# Sheet1.net
KiCad netlist of a schematic drawn in Altium Designer
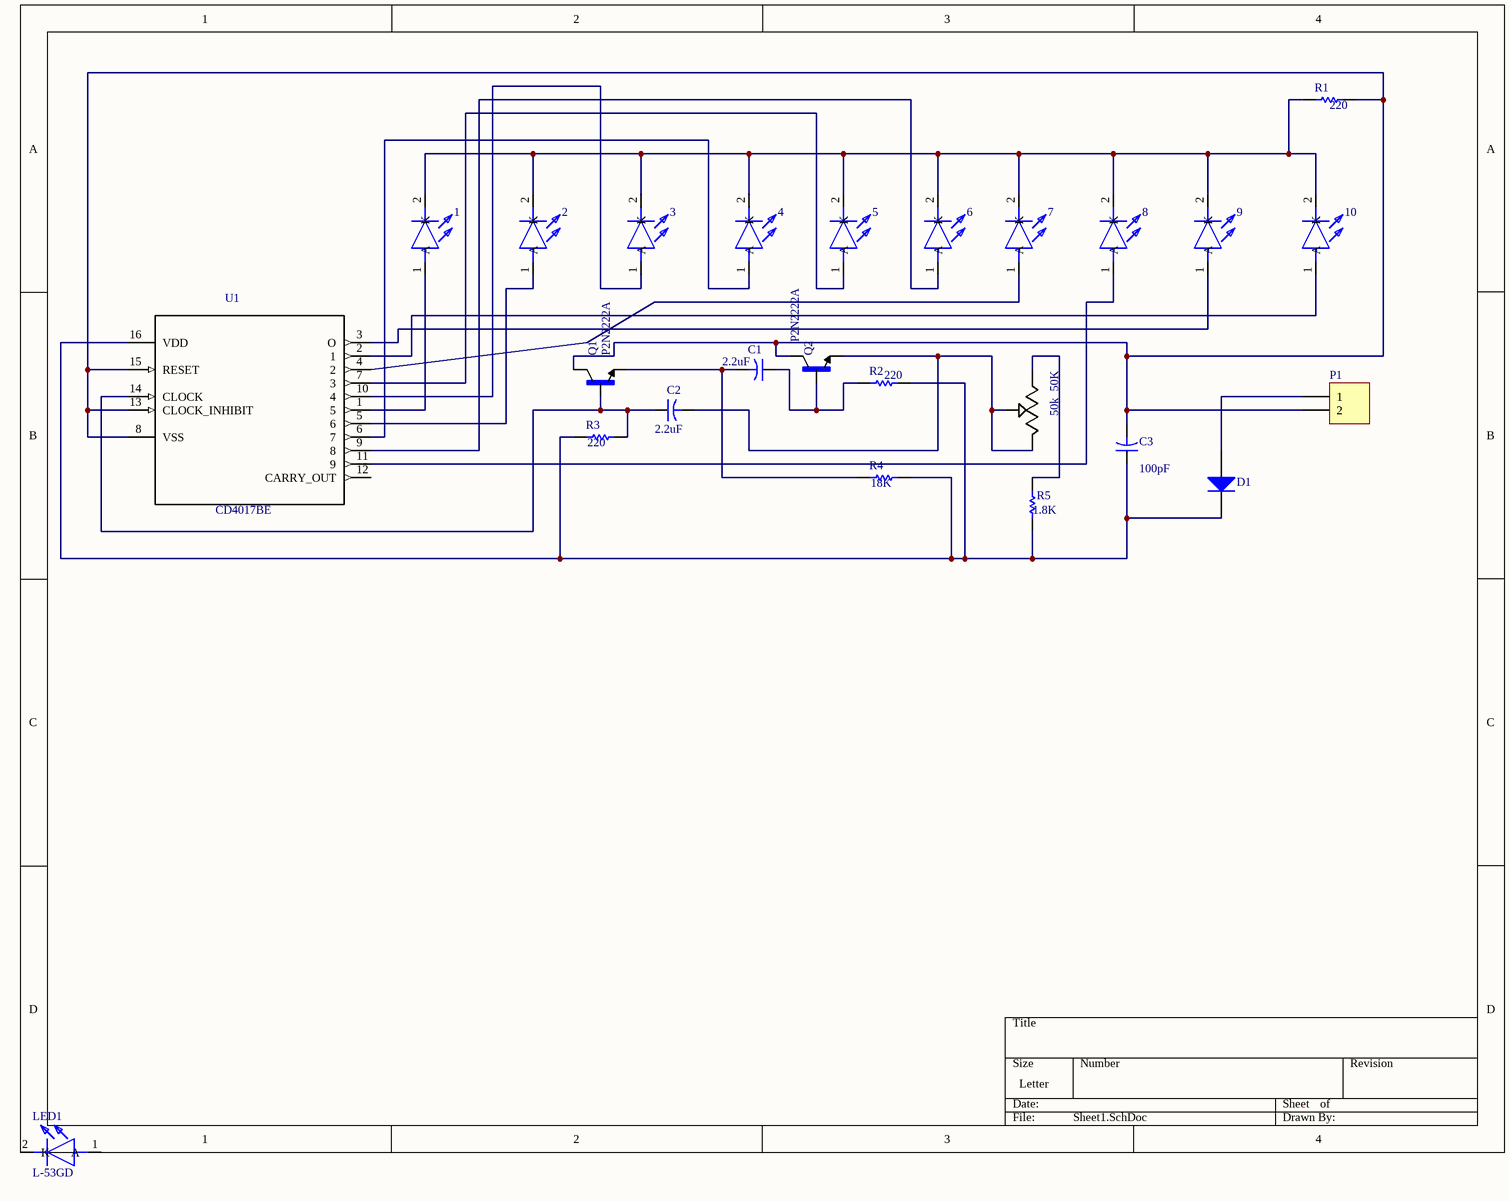
[diagram p0: Sheet1.SchDoc]

(export (version "E")
  (design (tool "Eeschema 10.0.6"))
  (components
    (comp (ref "1")
      (value "L-53GD")
      (footprint "SamacSys:L-53GD")
      (description "LED")
      (fields (field (name "RS PART NUMBER") "2286004A"))
      (libsource (lib "SamacSys") (part "L-53GD"))
    )
    (comp (ref "2")
      (value "L-53GD")
      (footprint "SamacSys:L-53GD")
      (description "LED")
      (fields (field (name "RS PART NUMBER") "2286004A"))
      (libsource (lib "SamacSys") (part "L-53GD"))
    )
    (comp (ref "3")
      (value "L-53GD")
      (footprint "SamacSys:L-53GD")
      (description "LED")
      (fields (field (name "RS PART NUMBER") "2286004A"))
      (libsource (lib "SamacSys") (part "L-53GD"))
    )
    (comp (ref "4")
      (value "L-53GD")
      (footprint "SamacSys:L-53GD")
      (description "LED")
      (fields (field (name "RS PART NUMBER") "2286004A"))
      (libsource (lib "SamacSys") (part "L-53GD"))
    )
    (comp (ref "5")
      (value "L-53GD")
      (footprint "SamacSys:L-53GD")
      (description "LED")
      (fields (field (name "RS PART NUMBER") "2286004A"))
      (libsource (lib "SamacSys") (part "L-53GD"))
    )
    (comp (ref "6")
      (value "L-53GD")
      (footprint "SamacSys:L-53GD")
      (description "LED")
      (fields (field (name "RS PART NUMBER") "2286004A"))
      (libsource (lib "SamacSys") (part "L-53GD"))
    )
    (comp (ref "7")
      (value "L-53GD")
      (footprint "SamacSys:L-53GD")
      (description "LED")
      (fields (field (name "RS PART NUMBER") "2286004A"))
      (libsource (lib "SamacSys") (part "L-53GD"))
    )
    (comp (ref "8")
      (value "L-53GD")
      (footprint "SamacSys:L-53GD")
      (description "LED")
      (fields (field (name "RS PART NUMBER") "2286004A"))
      (libsource (lib "SamacSys") (part "L-53GD"))
    )
    (comp (ref "9")
      (value "L-53GD")
      (footprint "SamacSys:L-53GD")
      (description "LED")
      (fields (field (name "RS PART NUMBER") "2286004A"))
      (libsource (lib "SamacSys") (part "L-53GD"))
    )
    (comp (ref "10")
      (value "L-53GD")
      (footprint "SamacSys:L-53GD")
      (description "LED")
      (fields (field (name "RS PART NUMBER") "2286004A"))
      (libsource (lib "SamacSys") (part "L-53GD"))
    )
    (comp (ref "50k")
      (value "50K")
      (footprint "*TRIM_EVN-D8AA03B14")
      (description "Trimmer; Carbon; Rest 10 Kilohms; PCB; 1 Turn; Pwr-Rtg 0.1 W; Linear; Top Adj; 6 mm SQ")
      (fields (field (name "MF") "Panasonic Electronic") (field (name "MP") "EVN-D8AA03B14"))
      (libsource (lib "EVN-D8AA03B14") (part "EVN-D8AA03B14"))
    )
    (comp (ref "C1")
      (value "2.2uF")
      (footprint "CAPR5-4X5")
      (description "Capacitor")
      (fields (field (name "PUBLISHER") "Altium Limited"))
      (libsource (lib "Miscellaneous Devices") (part "Cap2"))
    )
    (comp (ref "C2")
      (value "2.2uF")
      (footprint "CAPR5-4X5")
      (description "Capacitor")
      (fields (field (name "PUBLISHER") "Altium Limited"))
      (libsource (lib "Miscellaneous Devices") (part "Cap2"))
    )
    (comp (ref "C3")
      (value "100pF")
      (footprint "CAPR5-4X5")
      (description "Capacitor")
      (fields (field (name "PUBLISHER") "Altium Limited"))
      (libsource (lib "Miscellaneous Devices") (part "Cap2"))
    )
    (comp (ref "D1")
      (value "~")
      (footprint "DO-41")
      (description "1 Amp General Purpose Rectifier")
      (fields (field (name "PUBLISHER") "Altium Limited"))
      (libsource (lib "Miscellaneous Devices") (part "Diode 1N4001"))
    )
    (comp (ref "LED1")
      (value "L-53GD")
      (footprint "SamacSys:L-53GD")
      (description "LED")
      (fields (field (name "RS PART NUMBER") "2286004A"))
      (libsource (lib "*") (part "L-53GD"))
    )
    (comp (ref "P1")
      (value "~")
      (footprint "HDR1X2")
      (description "Header, 2-Pin")
      (fields (field (name "PUBLISHER") "Altium Limited"))
      (libsource (lib "Miscellaneous Connectors") (part "Header 2"))
    )
    (comp (ref "Q1")
      (value "P2N2222A")
      (footprint "*TO92")
      (fields (field (name "MF") "ON Semiconductor"))
      (libsource (lib "P2N2222A") (part "P2N2222A"))
    )
    (comp (ref "Q2")
      (value "P2N2222A")
      (footprint "*TO92")
      (fields (field (name "MF") "ON Semiconductor"))
      (libsource (lib "P2N2222A") (part "P2N2222A"))
    )
    (comp (ref "R1")
      (value "220")
      (footprint "AXIAL-0.3")
      (description "Resistor")
      (fields (field (name "PUBLISHER") "Altium Limited"))
      (libsource (lib "Miscellaneous Devices") (part "Res1"))
    )
    (comp (ref "R2")
      (value "220")
      (footprint "AXIAL-0.3")
      (description "Resistor")
      (fields (field (name "PUBLISHER") "Altium Limited"))
      (libsource (lib "Miscellaneous Devices") (part "Res1"))
    )
    (comp (ref "R3")
      (value "220")
      (footprint "AXIAL-0.3")
      (description "Resistor")
      (fields (field (name "PUBLISHER") "Altium Limited"))
      (libsource (lib "Miscellaneous Devices") (part "Res1"))
    )
    (comp (ref "R4")
      (value "18K")
      (footprint "AXIAL-0.3")
      (description "Resistor")
      (fields (field (name "PUBLISHER") "Altium Limited"))
      (libsource (lib "Miscellaneous Devices") (part "Res1"))
    )
    (comp (ref "R5")
      (value "1.8K")
      (footprint "AXIAL-0.3")
      (description "Resistor")
      (fields (field (name "PUBLISHER") "Altium Limited"))
      (libsource (lib "Miscellaneous Devices") (part "Res1"))
    )
    (comp (ref "U1")
      (value "CD4017BE")
      (footprint "*DIP254P762X508-16")
      (description "IC Mos 4017/CD4017BE HARRIS")
      (fields (field (name "MF") "Texas"))
      (libsource (lib "CD4017BE") (part "CD4017BE"))
    )
  )
  (nets
    (net (code "1") (name "Net-(1-A)") (class "Default")
      (node (ref "1") (pin "1") (pinfunction "A_1") (pintype "passive"))
      (node (ref "U1") (pin "1") (pinfunction "5_1") (pintype "output"))
    )
    (net (code "2") (name "Net-(1-K)") (class "Default")
      (node (ref "1") (pin "2") (pinfunction "K_2") (pintype "passive"))
      (node (ref "10") (pin "2") (pinfunction "K_2") (pintype "passive"))
      (node (ref "2") (pin "2") (pinfunction "K_2") (pintype "passive"))
      (node (ref "3") (pin "2") (pinfunction "K_2") (pintype "passive"))
      (node (ref "4") (pin "2") (pinfunction "K_2") (pintype "passive"))
      (node (ref "5") (pin "2") (pinfunction "K_2") (pintype "passive"))
      (node (ref "6") (pin "2") (pinfunction "K_2") (pintype "passive"))
      (node (ref "7") (pin "2") (pinfunction "K_2") (pintype "passive"))
      (node (ref "8") (pin "2") (pinfunction "K_2") (pintype "passive"))
      (node (ref "9") (pin "2") (pinfunction "K_2") (pintype "passive"))
      (node (ref "R1") (pin "1") (pinfunction "1_1") (pintype "passive"))
    )
    (net (code "3") (name "Net-(2-A)") (class "Default")
      (node (ref "2") (pin "1") (pinfunction "A_1") (pintype "passive"))
      (node (ref "U1") (pin "5") (pinfunction "6_5") (pintype "output"))
    )
    (net (code "4") (name "Net-(3-A)") (class "Default")
      (node (ref "3") (pin "1") (pinfunction "A_1") (pintype "passive"))
      (node (ref "U1") (pin "10") (pinfunction "4_10") (pintype "output"))
    )
    (net (code "5") (name "Net-(4-A)") (class "Default")
      (node (ref "4") (pin "1") (pinfunction "A_1") (pintype "passive"))
      (node (ref "U1") (pin "6") (pinfunction "7_6") (pintype "output"))
    )
    (net (code "6") (name "Net-(5-A)") (class "Default")
      (node (ref "5") (pin "1") (pinfunction "A_1") (pintype "passive"))
      (node (ref "U1") (pin "7") (pinfunction "3_7") (pintype "output"))
    )
    (net (code "7") (name "Net-(6-A)") (class "Default")
      (node (ref "6") (pin "1") (pinfunction "A_1") (pintype "passive"))
      (node (ref "U1") (pin "9") (pinfunction "8_9") (pintype "output"))
    )
    (net (code "8") (name "Net-(7-A)") (class "Default")
      (node (ref "7") (pin "1") (pinfunction "A_1") (pintype "passive"))
      (node (ref "U1") (pin "4") (pinfunction "2_4") (pintype "output"))
    )
    (net (code "9") (name "Net-(8-A)") (class "Default")
      (node (ref "8") (pin "1") (pinfunction "A_1") (pintype "passive"))
      (node (ref "U1") (pin "11") (pinfunction "9_11") (pintype "output"))
    )
    (net (code "10") (name "Net-(9-A)") (class "Default")
      (node (ref "9") (pin "1") (pinfunction "A_1") (pintype "passive"))
      (node (ref "U1") (pin "3") (pinfunction "O_3") (pintype "output"))
    )
    (net (code "11") (name "Net-(10-A)") (class "Default")
      (node (ref "10") (pin "1") (pinfunction "A_1") (pintype "passive"))
      (node (ref "U1") (pin "2") (pinfunction "1_2") (pintype "output"))
    )
    (net (code "12") (name "Net-(50k-Pad1)") (class "Default")
      (node (ref "50k") (pin "1") (pinfunction "1_1") (pintype "passive"))
      (node (ref "R5") (pin "1") (pinfunction "1_1") (pintype "passive"))
    )
    (net (code "13") (name "Net-(D1-A)") (class "Default")
      (node (ref "D1") (pin "1") (pinfunction "A_1") (pintype "passive"))
      (node (ref "P1") (pin "1") (pinfunction "1_1") (pintype "passive"))
    )
    (net (code "14") (name "Net-(D1-K)") (class "Default")
      (node (ref "C3") (pin "1") (pinfunction "1_1") (pintype "passive"))
      (node (ref "D1") (pin "2") (pinfunction "K_2") (pintype "passive"))
      (node (ref "R2") (pin "2") (pinfunction "2_2") (pintype "passive"))
      (node (ref "R3") (pin "1") (pinfunction "1_1") (pintype "passive"))
      (node (ref "R4") (pin "2") (pinfunction "2_2") (pintype "passive"))
      (node (ref "R5") (pin "2") (pinfunction "2_2") (pintype "passive"))
      (node (ref "U1") (pin "16") (pinfunction "VDD_16") (pintype "power_in"))
    )
    (net (code "15") (name "Net-(Q1-B)") (class "Default")
      (node (ref "C2") (pin "1") (pinfunction "1_1") (pintype "passive"))
      (node (ref "Q1") (pin "2") (pinfunction "B_2") (pintype "passive"))
      (node (ref "R3") (pin "2") (pinfunction "2_2") (pintype "passive"))
      (node (ref "U1") (pin "14") (pinfunction "CLOCK_14") (pintype "input"))
    )
    (net (code "16") (name "Net-(Q1-C)") (class "Default")
      (node (ref "C3") (pin "2") (pinfunction "2_2") (pintype "passive"))
      (node (ref "P1") (pin "2") (pinfunction "2_2") (pintype "passive"))
      (node (ref "Q1") (pin "3") (pinfunction "C_3") (pintype "passive"))
      (node (ref "Q2") (pin "3") (pinfunction "C_3") (pintype "passive"))
      (node (ref "R1") (pin "2") (pinfunction "2_2") (pintype "passive"))
      (node (ref "U1") (pin "13") (pinfunction "CLOCK_INHIBIT_13") (pintype "input"))
      (node (ref "U1") (pin "15") (pinfunction "RESET_15") (pintype "input"))
      (node (ref "U1") (pin "8") (pinfunction "VSS_8") (pintype "power_in"))
    )
    (net (code "17") (name "Net-(Q1-E)") (class "Default")
      (node (ref "C1") (pin "2") (pinfunction "2_2") (pintype "passive"))
      (node (ref "Q1") (pin "1") (pinfunction "E_1") (pintype "passive"))
      (node (ref "R4") (pin "1") (pinfunction "1_1") (pintype "passive"))
    )
    (net (code "18") (name "Net-(Q2-B)") (class "Default")
      (node (ref "C1") (pin "1") (pinfunction "1_1") (pintype "passive"))
      (node (ref "Q2") (pin "2") (pinfunction "B_2") (pintype "passive"))
      (node (ref "R2") (pin "1") (pinfunction "1_1") (pintype "passive"))
    )
    (net (code "19") (name "Net-(Q2-E)") (class "Default")
      (node (ref "50k") (pin "2") (pinfunction "2_2") (pintype "passive"))
      (node (ref "50k") (pin "3") (pinfunction "3_3") (pintype "passive"))
      (node (ref "C2") (pin "2") (pinfunction "2_2") (pintype "passive"))
      (node (ref "Q2") (pin "1") (pinfunction "E_1") (pintype "passive"))
    )
    (net (code "20") (name "unconnected-(LED1-A-Pad1)") (class "Default")
      (node (ref "LED1") (pin "1") (pinfunction "A_1") (pintype "passive"))
    )
    (net (code "21") (name "unconnected-(LED1-K-Pad2)") (class "Default")
      (node (ref "LED1") (pin "2") (pinfunction "K_2") (pintype "passive"))
    )
    (net (code "22") (name "unconnected-(U1-CARRY_OUT-Pad12)") (class "Default")
      (node (ref "U1") (pin "12") (pinfunction "CARRY_OUT_12") (pintype "output"))
    )
  )
)
